# HDMI_To_AV.net
KiCad netlist of a schematic drawn in EasyEDA Pro
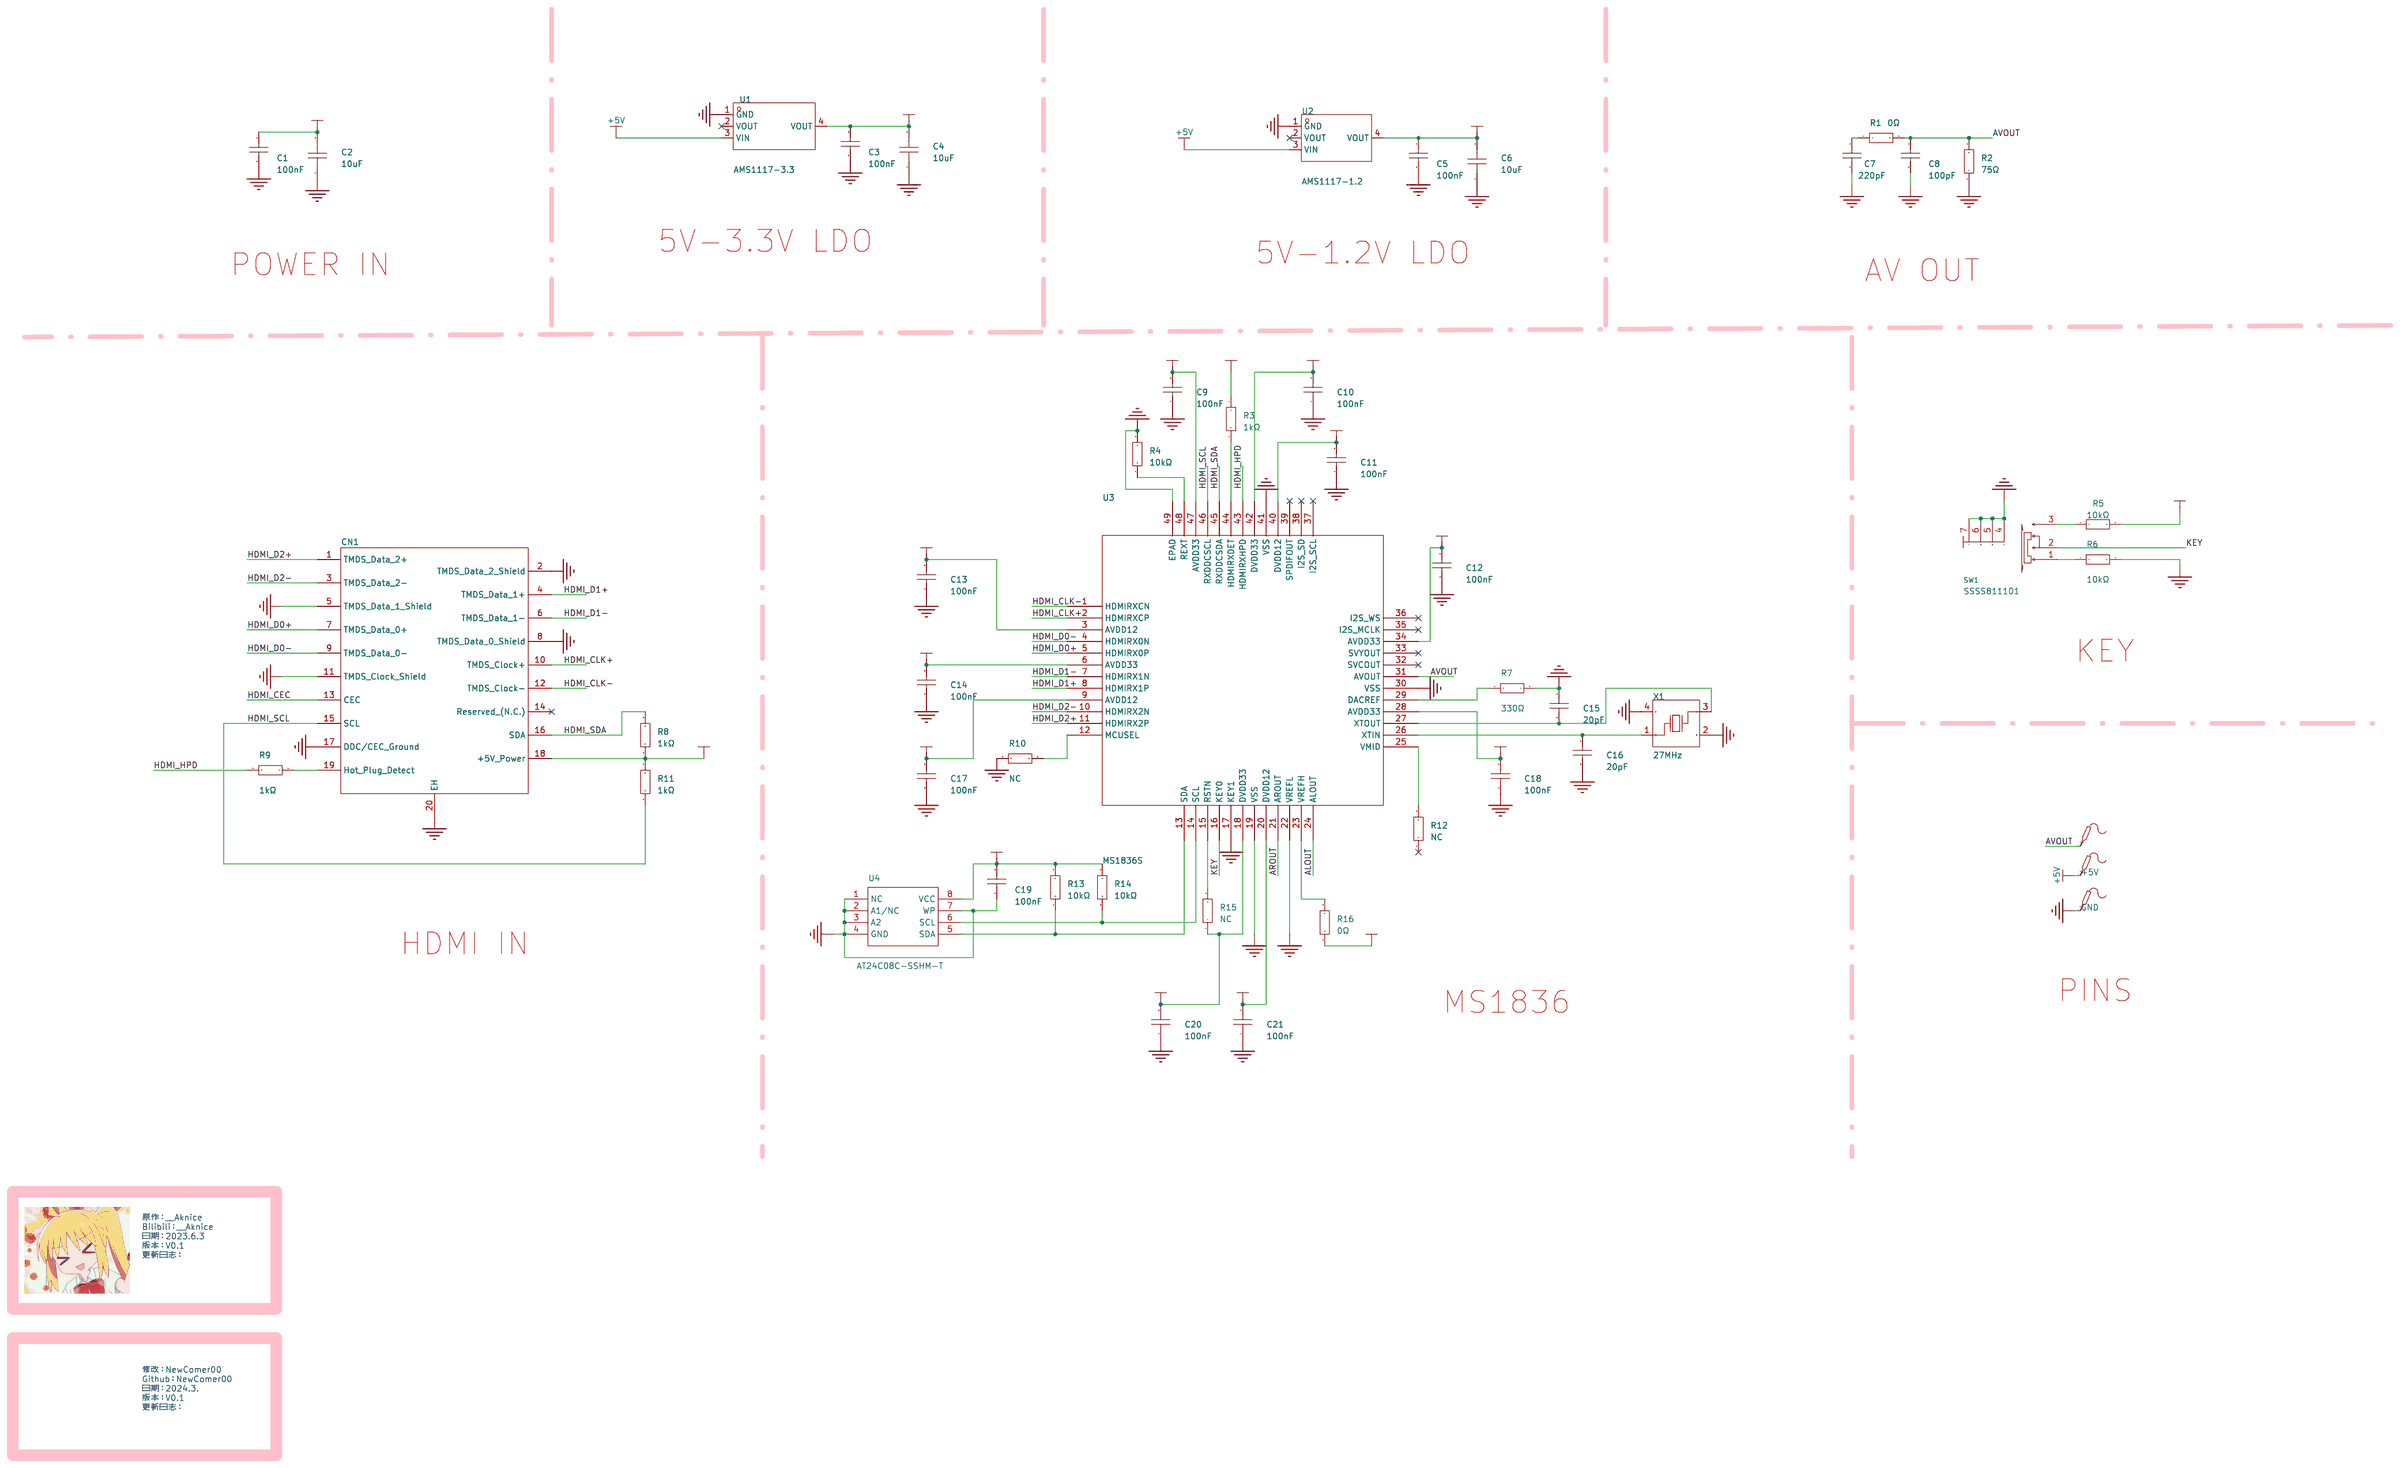
[diagram p0: schematic sheet]

(export (version "E")
  (design (tool "Eeschema 10.0.6"))
  (components
    (comp (ref "+5V")
      (value "~")
      (footprint "easyedapro:Test-Point-0.5mm")
      (description "Test Point 测试点")
      (libsource (lib "easyedapro") (part "Test-Point"))
    )
    (comp (ref "AVOUT")
      (value "~")
      (footprint "easyedapro:Test-Point-0.5mm")
      (description "Test Point 测试点")
      (libsource (lib "easyedapro") (part "Test-Point"))
    )
    (comp (ref "C1")
      (value "100nF")
      (footprint "easyedapro:C0402")
      (description "容值:100nF;精度:±10%;额定电压:16V;材质(温度系数):X7R;")
      (fields
        (field (name "Manufacturer Part") "CL05B104KO5NNNC")
        (field (name "Manufacturer") "SAMSUNG(三星)")
      )
      (libsource (lib "easyedapro") (part "CL05B104KO5NNNC"))
    )
    (comp (ref "C2")
      (value "10uF")
      (footprint "easyedapro:C0603")
      (description "容值:10uF;精度:±10%;额定电压:10V;材质(温度系数):X5R;")
      (fields
        (field (name "Manufacturer Part") "CL10A106KP8NNNC")
        (field (name "Manufacturer") "SAMSUNG(三星)")
      )
      (libsource (lib "easyedapro") (part "CL10A106KP8NNNC"))
    )
    (comp (ref "C3")
      (value "100nF")
      (footprint "easyedapro:C0402")
      (description "容值:100nF;精度:±10%;额定电压:16V;材质(温度系数):X7R;")
      (fields
        (field (name "Manufacturer Part") "CL05B104KO5NNNC")
        (field (name "Manufacturer") "SAMSUNG(三星)")
      )
      (libsource (lib "easyedapro") (part "CL05B104KO5NNNC"))
    )
    (comp (ref "C4")
      (value "10uF")
      (footprint "easyedapro:C0603")
      (description "容值:10uF;精度:±10%;额定电压:10V;材质(温度系数):X5R;")
      (fields
        (field (name "Manufacturer Part") "CL10A106KP8NNNC")
        (field (name "Manufacturer") "SAMSUNG(三星)")
      )
      (libsource (lib "easyedapro") (part "CL10A106KP8NNNC"))
    )
    (comp (ref "C5")
      (value "100nF")
      (footprint "easyedapro:C0402")
      (description "容值:100nF;精度:±10%;额定电压:16V;材质(温度系数):X7R;")
      (fields
        (field (name "Manufacturer Part") "CL05B104KO5NNNC")
        (field (name "Manufacturer") "SAMSUNG(三星)")
      )
      (libsource (lib "easyedapro") (part "CL05B104KO5NNNC"))
    )
    (comp (ref "C6")
      (value "10uF")
      (footprint "easyedapro:C0603")
      (description "容值:10uF;精度:±10%;额定电压:10V;材质(温度系数):X5R;")
      (fields
        (field (name "Manufacturer Part") "CL10A106KP8NNNC")
        (field (name "Manufacturer") "SAMSUNG(三星)")
      )
      (libsource (lib "easyedapro") (part "CL10A106KP8NNNC"))
    )
    (comp (ref "C7")
      (value "220pF")
      (footprint "easyedapro:C0402")
      (description "容值:220pF;精度:±10%;额定电压:50V;材质(温度系数):X7R;")
      (fields (field (name "Manufacturer Part") "0402B221K500NT") (field (name "Manufacturer") "FH(风华)"))
      (libsource (lib "easyedapro") (part "0402B221K500NT"))
    )
    (comp (ref "C8")
      (value "100pF")
      (footprint "easyedapro:C0402")
      (description "容值:100pF;精度:±5%;额定电压:50V;材质(温度系数):C0G;")
      (fields (field (name "Manufacturer Part") "0402CG101J500NT") (field (name "Manufacturer") "FH(风华)"))
      (libsource (lib "easyedapro") (part "0402CG101J500NT"))
    )
    (comp (ref "C9")
      (value "100nF")
      (footprint "easyedapro:C0402")
      (description "容值:100nF;精度:±10%;额定电压:16V;材质(温度系数):X7R;")
      (fields
        (field (name "Manufacturer Part") "CL05B104KO5NNNC")
        (field (name "Manufacturer") "SAMSUNG(三星)")
      )
      (libsource (lib "easyedapro") (part "CL05B104KO5NNNC"))
    )
    (comp (ref "C10")
      (value "100nF")
      (footprint "easyedapro:C0402")
      (description "容值:100nF;精度:±10%;额定电压:16V;材质(温度系数):X7R;")
      (fields
        (field (name "Manufacturer Part") "CL05B104KO5NNNC")
        (field (name "Manufacturer") "SAMSUNG(三星)")
      )
      (libsource (lib "easyedapro") (part "CL05B104KO5NNNC"))
    )
    (comp (ref "C11")
      (value "100nF")
      (footprint "easyedapro:C0402")
      (description "容值:100nF;精度:±10%;额定电压:16V;材质(温度系数):X7R;")
      (fields
        (field (name "Manufacturer Part") "CL05B104KO5NNNC")
        (field (name "Manufacturer") "SAMSUNG(三星)")
      )
      (libsource (lib "easyedapro") (part "CL05B104KO5NNNC"))
    )
    (comp (ref "C12")
      (value "100nF")
      (footprint "easyedapro:C0402")
      (description "容值:100nF;精度:±10%;额定电压:16V;材质(温度系数):X7R;")
      (fields
        (field (name "Manufacturer Part") "CL05B104KO5NNNC")
        (field (name "Manufacturer") "SAMSUNG(三星)")
      )
      (libsource (lib "easyedapro") (part "CL05B104KO5NNNC"))
    )
    (comp (ref "C13")
      (value "100nF")
      (footprint "easyedapro:C0402")
      (description "容值:100nF;精度:±10%;额定电压:16V;材质(温度系数):X7R;")
      (fields
        (field (name "Manufacturer Part") "CL05B104KO5NNNC")
        (field (name "Manufacturer") "SAMSUNG(三星)")
      )
      (libsource (lib "easyedapro") (part "CL05B104KO5NNNC"))
    )
    (comp (ref "C14")
      (value "100nF")
      (footprint "easyedapro:C0402")
      (description "容值:100nF;精度:±10%;额定电压:16V;材质(温度系数):X7R;")
      (fields
        (field (name "Manufacturer Part") "CL05B104KO5NNNC")
        (field (name "Manufacturer") "SAMSUNG(三星)")
      )
      (libsource (lib "easyedapro") (part "CL05B104KO5NNNC"))
    )
    (comp (ref "C15")
      (value "20pF")
      (footprint "easyedapro:C0402")
      (description "容值:20pF;精度:±5%;额定电压:50V;材质(温度系数):C0G;")
      (fields (field (name "Manufacturer Part") "0402CG200J500NT") (field (name "Manufacturer") "FH(风华)"))
      (libsource (lib "easyedapro") (part "0402CG200J500NT"))
    )
    (comp (ref "C16")
      (value "20pF")
      (footprint "easyedapro:C0402")
      (description "容值:20pF;精度:±5%;额定电压:50V;材质(温度系数):C0G;")
      (fields (field (name "Manufacturer Part") "0402CG200J500NT") (field (name "Manufacturer") "FH(风华)"))
      (libsource (lib "easyedapro") (part "0402CG200J500NT"))
    )
    (comp (ref "C17")
      (value "100nF")
      (footprint "easyedapro:C0402")
      (description "容值:100nF;精度:±10%;额定电压:16V;材质(温度系数):X7R;")
      (fields
        (field (name "Manufacturer Part") "CL05B104KO5NNNC")
        (field (name "Manufacturer") "SAMSUNG(三星)")
      )
      (libsource (lib "easyedapro") (part "CL05B104KO5NNNC"))
    )
    (comp (ref "C18")
      (value "100nF")
      (footprint "easyedapro:C0402")
      (description "容值:100nF;精度:±10%;额定电压:16V;材质(温度系数):X7R;")
      (fields
        (field (name "Manufacturer Part") "CL05B104KO5NNNC")
        (field (name "Manufacturer") "SAMSUNG(三星)")
      )
      (libsource (lib "easyedapro") (part "CL05B104KO5NNNC"))
    )
    (comp (ref "C19")
      (value "100nF")
      (footprint "easyedapro:C0402")
      (description "容值:100nF;精度:±10%;额定电压:16V;材质(温度系数):X7R;")
      (fields
        (field (name "Manufacturer Part") "CL05B104KO5NNNC")
        (field (name "Manufacturer") "SAMSUNG(三星)")
      )
      (libsource (lib "easyedapro") (part "CL05B104KO5NNNC"))
    )
    (comp (ref "C20")
      (value "100nF")
      (footprint "easyedapro:C0402")
      (description "容值:100nF;精度:±10%;额定电压:16V;材质(温度系数):X7R;")
      (fields
        (field (name "Manufacturer Part") "CL05B104KO5NNNC")
        (field (name "Manufacturer") "SAMSUNG(三星)")
      )
      (libsource (lib "easyedapro") (part "CL05B104KO5NNNC"))
    )
    (comp (ref "C21")
      (value "100nF")
      (footprint "easyedapro:C0402")
      (description "容值:100nF;精度:±10%;额定电压:16V;材质(温度系数):X7R;")
      (fields
        (field (name "Manufacturer Part") "CL05B104KO5NNNC")
        (field (name "Manufacturer") "SAMSUNG(三星)")
      )
      (libsource (lib "easyedapro") (part "CL05B104KO5NNNC"))
    )
    (comp (ref "CN1")
      (value "HDMI-019A")
      (footprint "easyedapro:HDMI-TH_HDMI-019A")
      (description "连接器类型:HDMI;公母:母;总PIN位数:19;排数:-;安装方式:弯插;额定电流:500mA;工作温度范围:-25~+75;")
      (fields (field (name "Manufacturer") "SOFNG(硕方)"))
      (libsource (lib "easyedapro") (part "HDMI-019A_C369072"))
    )
    (comp (ref "GND")
      (value "~")
      (footprint "easyedapro:Test-Point-0.5mm")
      (description "Test Point 测试点")
      (libsource (lib "easyedapro") (part "Test-Point"))
    )
    (comp (ref "R1")
      (value "0Ω")
      (footprint "easyedapro:R0805")
      (description "电阻类型:厚膜电阻;阻值:0Ω;精度:±1%;功率:125mW;")
      (fields
        (field (name "Manufacturer Part") "0805W8F0000T5E")
        (field (name "Manufacturer") "UNI-ROYAL(厚声)")
      )
      (libsource (lib "easyedapro") (part "0805W8F0000T5E"))
    )
    (comp (ref "R2")
      (value "75Ω")
      (footprint "easyedapro:R0402")
      (description "电阻类型:厚膜电阻;阻值:75Ω;精度:±1%;功率:62.5mW;")
      (fields
        (field (name "Manufacturer Part") "0402WGF750JTCE")
        (field (name "Manufacturer") "UNI-ROYAL(厚声)")
      )
      (libsource (lib "easyedapro") (part "0402WGF750JTCE"))
    )
    (comp (ref "R3")
      (value "1kΩ")
      (footprint "easyedapro:R0402")
      (description "电阻类型:厚膜电阻;阻值:1kΩ;精度:±5%;功率:62.5mW;")
      (fields
        (field (name "Manufacturer Part") "0402WGJ0102TCE")
        (field (name "Manufacturer") "UNI-ROYAL(厚声)")
      )
      (libsource (lib "easyedapro") (part "0402WGJ0102TCE"))
    )
    (comp (ref "R4")
      (value "10kΩ")
      (footprint "easyedapro:R0402")
      (description "电阻类型:厚膜电阻;阻值:10kΩ;精度:±1%;功率:62.5mW;")
      (fields
        (field (name "Manufacturer Part") "0402WGF1002TCE")
        (field (name "Manufacturer") "UNI-ROYAL(厚声)")
      )
      (libsource (lib "easyedapro") (part "0402WGF1002TCE"))
    )
    (comp (ref "R5")
      (value "10kΩ")
      (footprint "easyedapro:R0402")
      (description "电阻类型:厚膜电阻;阻值:10kΩ;精度:±1%;功率:62.5mW;")
      (fields
        (field (name "Manufacturer Part") "0402WGF1002TCE")
        (field (name "Manufacturer") "UNI-ROYAL(厚声)")
      )
      (libsource (lib "easyedapro") (part "0402WGF1002TCE"))
    )
    (comp (ref "R6")
      (value "10kΩ")
      (footprint "easyedapro:R0402")
      (description "电阻类型:厚膜电阻;阻值:10kΩ;精度:±1%;功率:62.5mW;")
      (fields
        (field (name "Manufacturer Part") "0402WGF1002TCE")
        (field (name "Manufacturer") "UNI-ROYAL(厚声)")
      )
      (libsource (lib "easyedapro") (part "0402WGF1002TCE"))
    )
    (comp (ref "R7")
      (value "330Ω")
      (footprint "easyedapro:R0402")
      (description "电阻类型:厚膜电阻;阻值:330Ω;精度:±1%;功率:62.5mW;")
      (fields
        (field (name "Manufacturer Part") "0402WGF3300TCE")
        (field (name "Manufacturer") "UNI-ROYAL(厚声)")
      )
      (libsource (lib "easyedapro") (part "0402WGF3300TCE"))
    )
    (comp (ref "R8")
      (value "1kΩ")
      (footprint "easyedapro:R0402")
      (description "电阻类型:厚膜电阻;阻值:1kΩ;精度:±5%;功率:62.5mW;")
      (fields
        (field (name "Manufacturer Part") "0402WGJ0102TCE")
        (field (name "Manufacturer") "UNI-ROYAL(厚声)")
      )
      (libsource (lib "easyedapro") (part "0402WGJ0102TCE"))
    )
    (comp (ref "R9")
      (value "1kΩ")
      (footprint "easyedapro:R0402")
      (description "电阻类型:厚膜电阻;阻值:1kΩ;精度:±5%;功率:62.5mW;")
      (fields
        (field (name "Manufacturer Part") "0402WGJ0102TCE")
        (field (name "Manufacturer") "UNI-ROYAL(厚声)")
      )
      (libsource (lib "easyedapro") (part "0402WGJ0102TCE"))
    )
    (comp (ref "R10")
      (value "NC")
      (footprint "easyedapro:R0402")
      (description "电阻类型:厚膜电阻;阻值:0Ω;精度:±1%;功率:62.5mW;")
      (fields
        (field (name "Manufacturer Part") "0402WGF0000TCE")
        (field (name "Manufacturer") "UNI-ROYAL(厚声)")
      )
      (libsource (lib "easyedapro") (part "0402WGF0000TCE"))
    )
    (comp (ref "R11")
      (value "1kΩ")
      (footprint "easyedapro:R0402")
      (description "电阻类型:厚膜电阻;阻值:1kΩ;精度:±5%;功率:62.5mW;")
      (fields
        (field (name "Manufacturer Part") "0402WGJ0102TCE")
        (field (name "Manufacturer") "UNI-ROYAL(厚声)")
      )
      (libsource (lib "easyedapro") (part "0402WGJ0102TCE"))
    )
    (comp (ref "R12")
      (value "NC")
      (footprint "easyedapro:R0402")
      (description "电阻类型:厚膜电阻;阻值:0Ω;精度:±1%;功率:62.5mW;")
      (fields
        (field (name "Manufacturer Part") "0402WGF0000TCE")
        (field (name "Manufacturer") "UNI-ROYAL(厚声)")
      )
      (libsource (lib "easyedapro") (part "0402WGF0000TCE"))
    )
    (comp (ref "R13")
      (value "10kΩ")
      (footprint "easyedapro:R0402")
      (description "电阻类型:厚膜电阻;阻值:10kΩ;精度:±1%;功率:62.5mW;")
      (fields
        (field (name "Manufacturer Part") "0402WGF1002TCE")
        (field (name "Manufacturer") "UNI-ROYAL(厚声)")
      )
      (libsource (lib "easyedapro") (part "0402WGF1002TCE"))
    )
    (comp (ref "R14")
      (value "10kΩ")
      (footprint "easyedapro:R0402")
      (description "电阻类型:厚膜电阻;阻值:10kΩ;精度:±1%;功率:62.5mW;")
      (fields
        (field (name "Manufacturer Part") "0402WGF1002TCE")
        (field (name "Manufacturer") "UNI-ROYAL(厚声)")
      )
      (libsource (lib "easyedapro") (part "0402WGF1002TCE"))
    )
    (comp (ref "R15")
      (value "NC")
      (footprint "easyedapro:R0402")
      (description "电阻类型:厚膜电阻;阻值:0Ω;精度:±1%;功率:62.5mW;")
      (fields
        (field (name "Manufacturer Part") "0402WGF0000TCE")
        (field (name "Manufacturer") "UNI-ROYAL(厚声)")
      )
      (libsource (lib "easyedapro") (part "0402WGF0000TCE"))
    )
    (comp (ref "R16")
      (value "0Ω")
      (footprint "easyedapro:R0402")
      (description "电阻类型:厚膜电阻;阻值:0Ω;精度:±1%;功率:62.5mW;")
      (fields
        (field (name "Manufacturer Part") "0402WGF0000TCE")
        (field (name "Manufacturer") "UNI-ROYAL(厚声)")
      )
      (libsource (lib "easyedapro") (part "0402WGF0000TCE"))
    )
    (comp (ref "SW1")
      (value "SSSS811101")
      (footprint "easyedapro:SW-SMD_SSSS811101")
      (description "电路结构:单刀双掷;安装方式:卧贴;额定电流(DC):300mA;额定电压(DC):5V;额定电流(AC):-;额定电压(AC):-;机械寿命:1万次;")
      (fields (field (name "Manufacturer") "ALPSALPINE(阿尔卑斯阿尔派)"))
      (libsource (lib "easyedapro") (part "SSSS811101"))
    )
    (comp (ref "U1")
      (value "AMS1117-3.3")
      (footprint "easyedapro:SOT-223-3_L6.5-W3.4-P2.30-LS7.0-BR")
      (description "输出类型:固定;输出极性:正;最大输入电压:-;输出电压:3.3V;输出电流:1A;电源纹波抑制比(PSRR):72dB@(120Hz);")
      (fields (field (name "Manufacturer") "AMS"))
      (libsource (lib "easyedapro") (part "AMS1117-3.3"))
    )
    (comp (ref "U2")
      (value "AMS1117-1.2")
      (footprint "easyedapro:SOT-223-3_L6.7-W3.7-P2.30-LS7.0-BR")
      (description "输出类型:-;")
      (fields (field (name "Manufacturer") "JSMSEMI(杰盛微)"))
      (libsource (lib "easyedapro") (part "AMS1117-1.2_C963402"))
    )
    (comp (ref "U3")
      (value "MS1836S")
      (footprint "easyedapro:QFN48-Normal")
      (libsource (lib "easyedapro") (part "MS1836S"))
    )
    (comp (ref "U4")
      (value "AT24C08C-SSHM-T")
      (footprint "easyedapro:SOIC-8_L5.0-W4.0-P1.27-LS6.0-BL")
      (description "接口类型:I2C;存储容量:8Kbit;")
      (fields (field (name "Manufacturer") "MICROCHIP(美国微芯)"))
      (libsource (lib "easyedapro") (part "AT24C08C-SSHM-T"))
    )
    (comp (ref "X1")
      (value "27MHz")
      (footprint "easyedapro:OSC-SMD_4P-L3.2-W2.5-BL")
      (description "频率:27MHz;频率公差:±10ppm;负载电容:20pF;")
      (fields (field (name "Manufacturer Part") "X322527MSB4SI") (field (name "Manufacturer") "YXC(扬兴晶振)"))
      (libsource (lib "easyedapro") (part "X322527MSB4SI"))
    )
  )
  (nets
    (net (code "1") (name "+1.2V") (class "Default")
      (node (ref "C11") (pin "2") (pinfunction "2_2") (pintype "input"))
      (node (ref "C13") (pin "2") (pinfunction "2_2") (pintype "input"))
      (node (ref "C17") (pin "2") (pinfunction "2_2") (pintype "input"))
      (node (ref "C21") (pin "2") (pinfunction "2_2") (pintype "input"))
      (node (ref "C5") (pin "2") (pinfunction "2_2") (pintype "input"))
      (node (ref "C6") (pin "2") (pinfunction "2_2") (pintype "input"))
      (node (ref "U2") (pin "4") (pinfunction "VOUT_4") (pintype "input"))
      (node (ref "U3") (pin "20") (pinfunction "DVDD12_20") (pintype "input"))
      (node (ref "U3") (pin "3") (pinfunction "AVDD12_3") (pintype "input"))
      (node (ref "U3") (pin "40") (pinfunction "DVDD12_40") (pintype "input"))
      (node (ref "U3") (pin "9") (pinfunction "AVDD12_9") (pintype "input"))
    )
    (net (code "2") (name "+3.3V") (class "Default")
      (node (ref "C10") (pin "2") (pinfunction "2_2") (pintype "input"))
      (node (ref "C12") (pin "2") (pinfunction "2_2") (pintype "input"))
      (node (ref "C14") (pin "2") (pinfunction "2_2") (pintype "input"))
      (node (ref "C18") (pin "2") (pinfunction "2_2") (pintype "input"))
      (node (ref "C19") (pin "2") (pinfunction "2_2") (pintype "input"))
      (node (ref "C20") (pin "2") (pinfunction "2_2") (pintype "input"))
      (node (ref "C3") (pin "2") (pinfunction "2_2") (pintype "input"))
      (node (ref "C4") (pin "2") (pinfunction "2_2") (pintype "input"))
      (node (ref "C9") (pin "2") (pinfunction "2_2") (pintype "input"))
      (node (ref "R13") (pin "2") (pinfunction "2_2") (pintype "input"))
      (node (ref "R14") (pin "2") (pinfunction "2_2") (pintype "input"))
      (node (ref "R15") (pin "1") (pinfunction "1_1") (pintype "input"))
      (node (ref "R16") (pin "1") (pinfunction "1_1") (pintype "input"))
      (node (ref "R5") (pin "2") (pinfunction "2_2") (pintype "input"))
      (node (ref "U1") (pin "4") (pinfunction "VOUT_4") (pintype "input"))
      (node (ref "U3") (pin "18") (pinfunction "DVDD33_18") (pintype "input"))
      (node (ref "U3") (pin "28") (pinfunction "AVDD33_28") (pintype "input"))
      (node (ref "U3") (pin "34") (pinfunction "AVDD33_34") (pintype "input"))
      (node (ref "U3") (pin "42") (pinfunction "DVDD33_42") (pintype "input"))
      (node (ref "U3") (pin "47") (pinfunction "AVDD33_47") (pintype "input"))
      (node (ref "U3") (pin "6") (pinfunction "AVDD33_6") (pintype "input"))
      (node (ref "U4") (pin "8") (pinfunction "VCC_8") (pintype "input"))
    )
    (net (code "3") (name "+5V") (class "Default")
      (node (ref "+5V") (pin "1") (pinfunction "1_1") (pintype "input"))
      (node (ref "C1") (pin "2") (pinfunction "2_2") (pintype "input"))
      (node (ref "C2") (pin "2") (pinfunction "2_2") (pintype "input"))
      (node (ref "U1") (pin "3") (pinfunction "VIN_3") (pintype "input"))
      (node (ref "U2") (pin "3") (pinfunction "VIN_3") (pintype "input"))
    )
    (net (code "4") (name "/ALOUT") (class "Default")
      (node (ref "U3") (pin "24") (pinfunction "ALOUT_24") (pintype "output"))
    )
    (net (code "5") (name "/AROUT") (class "Default")
      (node (ref "U3") (pin "21") (pinfunction "AROUT_21") (pintype "output"))
    )
    (net (code "6") (name "/AVOUT") (class "Default")
      (node (ref "AVOUT") (pin "1") (pinfunction "1_1") (pintype "input"))
      (node (ref "C8") (pin "2") (pinfunction "2_2") (pintype "input"))
      (node (ref "R1") (pin "2") (pinfunction "2_2") (pintype "input"))
      (node (ref "R2") (pin "2") (pinfunction "2_2") (pintype "input"))
      (node (ref "U3") (pin "31") (pinfunction "AVOUT_31") (pintype "output"))
    )
    (net (code "7") (name "/HDMI_CEC") (class "Default")
      (node (ref "CN1") (pin "13") (pinfunction "CEC_13") (pintype "input"))
    )
    (net (code "8") (name "/HDMI_CLK+") (class "Default")
      (node (ref "CN1") (pin "10") (pinfunction "TMDS_Clock+_10") (pintype "input"))
      (node (ref "U3") (pin "2") (pinfunction "HDMIRXCP_2") (pintype "input"))
    )
    (net (code "9") (name "/HDMI_CLK-") (class "Default")
      (node (ref "CN1") (pin "12") (pinfunction "TMDS_Clock-_12") (pintype "input"))
      (node (ref "U3") (pin "1") (pinfunction "HDMIRXCN_1") (pintype "input"))
    )
    (net (code "10") (name "/HDMI_D0+") (class "Default")
      (node (ref "CN1") (pin "7") (pinfunction "TMDS_Data_0+_7") (pintype "input"))
      (node (ref "U3") (pin "5") (pinfunction "HDMIRX0P_5") (pintype "input"))
    )
    (net (code "11") (name "/HDMI_D0-") (class "Default")
      (node (ref "CN1") (pin "9") (pinfunction "TMDS_Data_0-_9") (pintype "input"))
      (node (ref "U3") (pin "4") (pinfunction "HDMIRX0N_4") (pintype "input"))
    )
    (net (code "12") (name "/HDMI_D1+") (class "Default")
      (node (ref "CN1") (pin "4") (pinfunction "TMDS_Data_1+_4") (pintype "input"))
      (node (ref "U3") (pin "8") (pinfunction "HDMIRX1P_8") (pintype "input"))
    )
    (net (code "13") (name "/HDMI_D1-") (class "Default")
      (node (ref "CN1") (pin "6") (pinfunction "TMDS_Data_1-_6") (pintype "input"))
      (node (ref "U3") (pin "7") (pinfunction "HDMIRX1N_7") (pintype "input"))
    )
    (net (code "14") (name "/HDMI_D2+") (class "Default")
      (node (ref "CN1") (pin "1") (pinfunction "TMDS_Data_2+_1") (pintype "input"))
      (node (ref "U3") (pin "11") (pinfunction "HDMIRX2P_11") (pintype "input"))
    )
    (net (code "15") (name "/HDMI_D2-") (class "Default")
      (node (ref "CN1") (pin "3") (pinfunction "TMDS_Data_2-_3") (pintype "input"))
      (node (ref "U3") (pin "10") (pinfunction "HDMIRX2N_10") (pintype "input"))
    )
    (net (code "16") (name "/HDMI_HPD") (class "Default")
      (node (ref "R9") (pin "2") (pinfunction "2_2") (pintype "input"))
      (node (ref "U3") (pin "43") (pinfunction "HDMIRXHPD_43") (pintype "output"))
    )
    (net (code "17") (name "/HDMI_SCL") (class "Default")
      (node (ref "CN1") (pin "15") (pinfunction "SCL_15") (pintype "input"))
      (node (ref "R11") (pin "1") (pinfunction "1_1") (pintype "input"))
      (node (ref "U3") (pin "46") (pinfunction "RXDDCSCL_46") (pintype "output"))
    )
    (net (code "18") (name "/HDMI_SDA") (class "Default")
      (node (ref "CN1") (pin "16") (pinfunction "SDA_16") (pintype "input"))
      (node (ref "R8") (pin "2") (pinfunction "2_2") (pintype "input"))
      (node (ref "U3") (pin "45") (pinfunction "RXDDCSDA_45") (pintype "input"))
    )
    (net (code "19") (name "/KEY") (class "Default")
      (node (ref "SW1") (pin "2") (pinfunction "2_2") (pintype "input"))
      (node (ref "U3") (pin "16") (pinfunction "KEY0_16") (pintype "input"))
    )
    (net (code "20") (name "GND") (class "Default")
      (node (ref "C1") (pin "1") (pinfunction "1_1") (pintype "input"))
      (node (ref "C10") (pin "1") (pinfunction "1_1") (pintype "input"))
      (node (ref "C11") (pin "1") (pinfunction "1_1") (pintype "input"))
      (node (ref "C12") (pin "1") (pinfunction "1_1") (pintype "input"))
      (node (ref "C13") (pin "1") (pinfunction "1_1") (pintype "input"))
      (node (ref "C14") (pin "1") (pinfunction "1_1") (pintype "input"))
      (node (ref "C15") (pin "2") (pinfunction "2_2") (pintype "input"))
      (node (ref "C16") (pin "1") (pinfunction "1_1") (pintype "input"))
      (node (ref "C17") (pin "1") (pinfunction "1_1") (pintype "input"))
      (node (ref "C18") (pin "1") (pinfunction "1_1") (pintype "input"))
      (node (ref "C19") (pin "1") (pinfunction "1_1") (pintype "input"))
      (node (ref "C2") (pin "1") (pinfunction "1_1") (pintype "input"))
      (node (ref "C20") (pin "1") (pinfunction "1_1") (pintype "input"))
      (node (ref "C21") (pin "1") (pinfunction "1_1") (pintype "input"))
      (node (ref "C3") (pin "1") (pinfunction "1_1") (pintype "input"))
      (node (ref "C4") (pin "1") (pinfunction "1_1") (pintype "input"))
      (node (ref "C5") (pin "1") (pinfunction "1_1") (pintype "input"))
      (node (ref "C6") (pin "1") (pinfunction "1_1") (pintype "input"))
      (node (ref "C7") (pin "1") (pinfunction "1_1") (pintype "input"))
      (node (ref "C8") (pin "1") (pinfunction "1_1") (pintype "input"))
      (node (ref "C9") (pin "1") (pinfunction "1_1") (pintype "input"))
      (node (ref "CN1") (pin "11") (pinfunction "TMDS_Clock_Shield_11") (pintype "input"))
      (node (ref "CN1") (pin "17") (pinfunction "DDC/CEC_Ground_17") (pintype "input"))
      (node (ref "CN1") (pin "2") (pinfunction "TMDS_Data_2_Shield_2") (pintype "input"))
      (node (ref "CN1") (pin "20") (pinfunction "EH_20") (pintype "input"))
      (node (ref "CN1") (pin "5") (pinfunction "TMDS_Data_1_Shield_5") (pintype "input"))
      (node (ref "CN1") (pin "8") (pinfunction "TMDS_Data_0_Shield_8") (pintype "input"))
      (node (ref "GND") (pin "1") (pinfunction "1_1") (pintype "input"))
      (node (ref "R10") (pin "2") (pinfunction "2_2") (pintype "input"))
      (node (ref "R2") (pin "1") (pinfunction "1_1") (pintype "input"))
      (node (ref "R4") (pin "2") (pinfunction "2_2") (pintype "input"))
      (node (ref "R6") (pin "2") (pinfunction "2_2") (pintype "input"))
      (node (ref "R7") (pin "2") (pinfunction "2_2") (pintype "input"))
      (node (ref "SW1") (pin "4") (pinfunction "4_4") (pintype "input"))
      (node (ref "SW1") (pin "5") (pinfunction "5_5") (pintype "input"))
      (node (ref "SW1") (pin "6") (pinfunction "6_6") (pintype "input"))
      (node (ref "SW1") (pin "7") (pinfunction "7_7") (pintype "input"))
      (node (ref "U1") (pin "1") (pinfunction "GND_1") (pintype "input"))
      (node (ref "U2") (pin "1") (pinfunction "GND_1") (pintype "input"))
      (node (ref "U3") (pin "17") (pinfunction "KEY1_17") (pintype "input"))
      (node (ref "U3") (pin "19") (pinfunction "VSS_19") (pintype "input"))
      (node (ref "U3") (pin "22") (pinfunction "VREFL_22") (pintype "input"))
      (node (ref "U3") (pin "30") (pinfunction "VSS_30") (pintype "input"))
      (node (ref "U3") (pin "41") (pinfunction "VSS_41") (pintype "input"))
      (node (ref "U3") (pin "49") (pinfunction "EPAD_49") (pintype "input"))
      (node (ref "U4") (pin "1") (pinfunction "NC_1") (pintype "input"))
      (node (ref "U4") (pin "2") (pinfunction "A1/NC_2") (pintype "input"))
      (node (ref "U4") (pin "3") (pinfunction "A2_3") (pintype "input"))
      (node (ref "U4") (pin "4") (pinfunction "GND_4") (pintype "input"))
      (node (ref "U4") (pin "7") (pinfunction "WP_7") (pintype "input"))
      (node (ref "X1") (pin "2") (pinfunction "GND_2") (pintype "input"))
      (node (ref "X1") (pin "4") (pinfunction "GND_4") (pintype "input"))
    )
    (net (code "21") (name "Net-(C7-Pad2)") (class "Default")
      (node (ref "C7") (pin "2") (pinfunction "2_2") (pintype "input"))
      (node (ref "R1") (pin "1") (pinfunction "1_1") (pintype "input"))
    )
    (net (code "22") (name "Net-(CN1-Hot_Plug_Detect)") (class "Default")
      (node (ref "CN1") (pin "19") (pinfunction "Hot_Plug_Detect_19") (pintype "input"))
      (node (ref "R9") (pin "1") (pinfunction "1_1") (pintype "input"))
    )
    (net (code "23") (name "Net-(R5-Pad1)") (class "Default")
      (node (ref "R5") (pin "1") (pinfunction "1_1") (pintype "input"))
      (node (ref "SW1") (pin "3") (pinfunction "3_3") (pintype "input"))
    )
    (net (code "24") (name "Net-(R6-Pad1)") (class "Default")
      (node (ref "R6") (pin "1") (pinfunction "1_1") (pintype "input"))
      (node (ref "SW1") (pin "1") (pinfunction "1_1") (pintype "input"))
    )
    (net (code "25") (name "Net-(U3-DACREF)") (class "Default")
      (node (ref "R7") (pin "1") (pinfunction "1_1") (pintype "input"))
      (node (ref "U3") (pin "29") (pinfunction "DACREF_29") (pintype "input"))
    )
    (net (code "26") (name "Net-(U3-HDMIRXDET)") (class "Default")
      (node (ref "R3") (pin "2") (pinfunction "2_2") (pintype "input"))
      (node (ref "U3") (pin "44") (pinfunction "HDMIRXDET_44") (pintype "input"))
    )
    (net (code "27") (name "Net-(U3-MCUSEL)") (class "Default")
      (node (ref "R10") (pin "1") (pinfunction "1_1") (pintype "input"))
      (node (ref "U3") (pin "12") (pinfunction "MCUSEL_12") (pintype "input"))
    )
    (net (code "28") (name "Net-(U3-REXT)") (class "Default")
      (node (ref "R4") (pin "1") (pinfunction "1_1") (pintype "input"))
      (node (ref "U3") (pin "48") (pinfunction "REXT_48") (pintype "input"))
    )
    (net (code "29") (name "Net-(U3-RSTN)") (class "Default")
      (node (ref "R15") (pin "2") (pinfunction "2_2") (pintype "input"))
      (node (ref "U3") (pin "15") (pinfunction "RSTN_15") (pintype "input"))
    )
    (net (code "30") (name "Net-(U3-SCL)") (class "Default")
      (node (ref "R14") (pin "1") (pinfunction "1_1") (pintype "input"))
      (node (ref "U3") (pin "14") (pinfunction "SCL_14") (pintype "output"))
      (node (ref "U4") (pin "6") (pinfunction "SCL_6") (pintype "input"))
    )
    (net (code "31") (name "Net-(U3-SDA)") (class "Default")
      (node (ref "R13") (pin "1") (pinfunction "1_1") (pintype "input"))
      (node (ref "U3") (pin "13") (pinfunction "SDA_13") (pintype "bidirectional"))
      (node (ref "U4") (pin "5") (pinfunction "SDA_5") (pintype "input"))
    )
    (net (code "32") (name "Net-(U3-VMID)") (class "Default")
      (node (ref "R12") (pin "2") (pinfunction "2_2") (pintype "input"))
      (node (ref "U3") (pin "25") (pinfunction "VMID_25") (pintype "input"))
    )
    (net (code "33") (name "Net-(U3-VREFH)") (class "Default")
      (node (ref "R16") (pin "2") (pinfunction "2_2") (pintype "input"))
      (node (ref "U3") (pin "23") (pinfunction "VREFH_23") (pintype "input"))
    )
    (net (code "34") (name "Net-(U3-XTIN)") (class "Default")
      (node (ref "C16") (pin "2") (pinfunction "2_2") (pintype "input"))
      (node (ref "U3") (pin "26") (pinfunction "XTIN_26") (pintype "input"))
      (node (ref "X1") (pin "1") (pinfunction "OSC1_1") (pintype "input"))
    )
    (net (code "35") (name "Net-(U3-XTOUT)") (class "Default")
      (node (ref "C15") (pin "1") (pinfunction "1_1") (pintype "input"))
      (node (ref "U3") (pin "27") (pinfunction "XTOUT_27") (pintype "input"))
      (node (ref "X1") (pin "3") (pinfunction "OSC2_3") (pintype "input"))
    )
    (net (code "36") (name "RX5V") (class "Default")
      (node (ref "CN1") (pin "18") (pinfunction "+5V_Power_18") (pintype "input"))
      (node (ref "R11") (pin "2") (pinfunction "2_2") (pintype "input"))
      (node (ref "R3") (pin "1") (pinfunction "1_1") (pintype "input"))
      (node (ref "R8") (pin "1") (pinfunction "1_1") (pintype "input"))
    )
    (net (code "37") (name "unconnected-(CN1-Reserved_(N.C.)-Pad14)") (class "Default")
      (node (ref "CN1") (pin "14") (pinfunction "Reserved_(N.C.)_14") (pintype "input+no_connect"))
    )
    (net (code "38") (name "unconnected-(R12-Pad1)") (class "Default")
      (node (ref "R12") (pin "1") (pinfunction "1_1") (pintype "input+no_connect"))
    )
    (net (code "39") (name "unconnected-(U1-VOUT-Pad2)") (class "Default")
      (node (ref "U1") (pin "2") (pinfunction "VOUT_2") (pintype "input+no_connect"))
    )
    (net (code "40") (name "unconnected-(U2-VOUT-Pad2)") (class "Default")
      (node (ref "U2") (pin "2") (pinfunction "VOUT_2") (pintype "input+no_connect"))
    )
    (net (code "41") (name "unconnected-(U3-I2S_MCLK-Pad35)") (class "Default")
      (node (ref "U3") (pin "35") (pinfunction "I2S_MCLK_35") (pintype "input+no_connect"))
    )
    (net (code "42") (name "unconnected-(U3-I2S_SCL-Pad37)") (class "Default")
      (node (ref "U3") (pin "37") (pinfunction "I2S_SCL_37") (pintype "input+no_connect"))
    )
    (net (code "43") (name "unconnected-(U3-I2S_SD-Pad38)") (class "Default")
      (node (ref "U3") (pin "38") (pinfunction "I2S_SD_38") (pintype "input+no_connect"))
    )
    (net (code "44") (name "unconnected-(U3-I2S_WS-Pad36)") (class "Default")
      (node (ref "U3") (pin "36") (pinfunction "I2S_WS_36") (pintype "input+no_connect"))
    )
    (net (code "45") (name "unconnected-(U3-SPDIFOUT-Pad39)") (class "Default")
      (node (ref "U3") (pin "39") (pinfunction "SPDIFOUT_39") (pintype "output+no_connect"))
    )
    (net (code "46") (name "unconnected-(U3-SVCOUT-Pad32)") (class "Default")
      (node (ref "U3") (pin "32") (pinfunction "SVCOUT_32") (pintype "output+no_connect"))
    )
    (net (code "47") (name "unconnected-(U3-SVYOUT-Pad33)") (class "Default")
      (node (ref "U3") (pin "33") (pinfunction "SVYOUT_33") (pintype "output+no_connect"))
    )
  )
)
